# LCD_ctrl_v2b.net
KiCad netlist of a schematic drawn in EAGLE
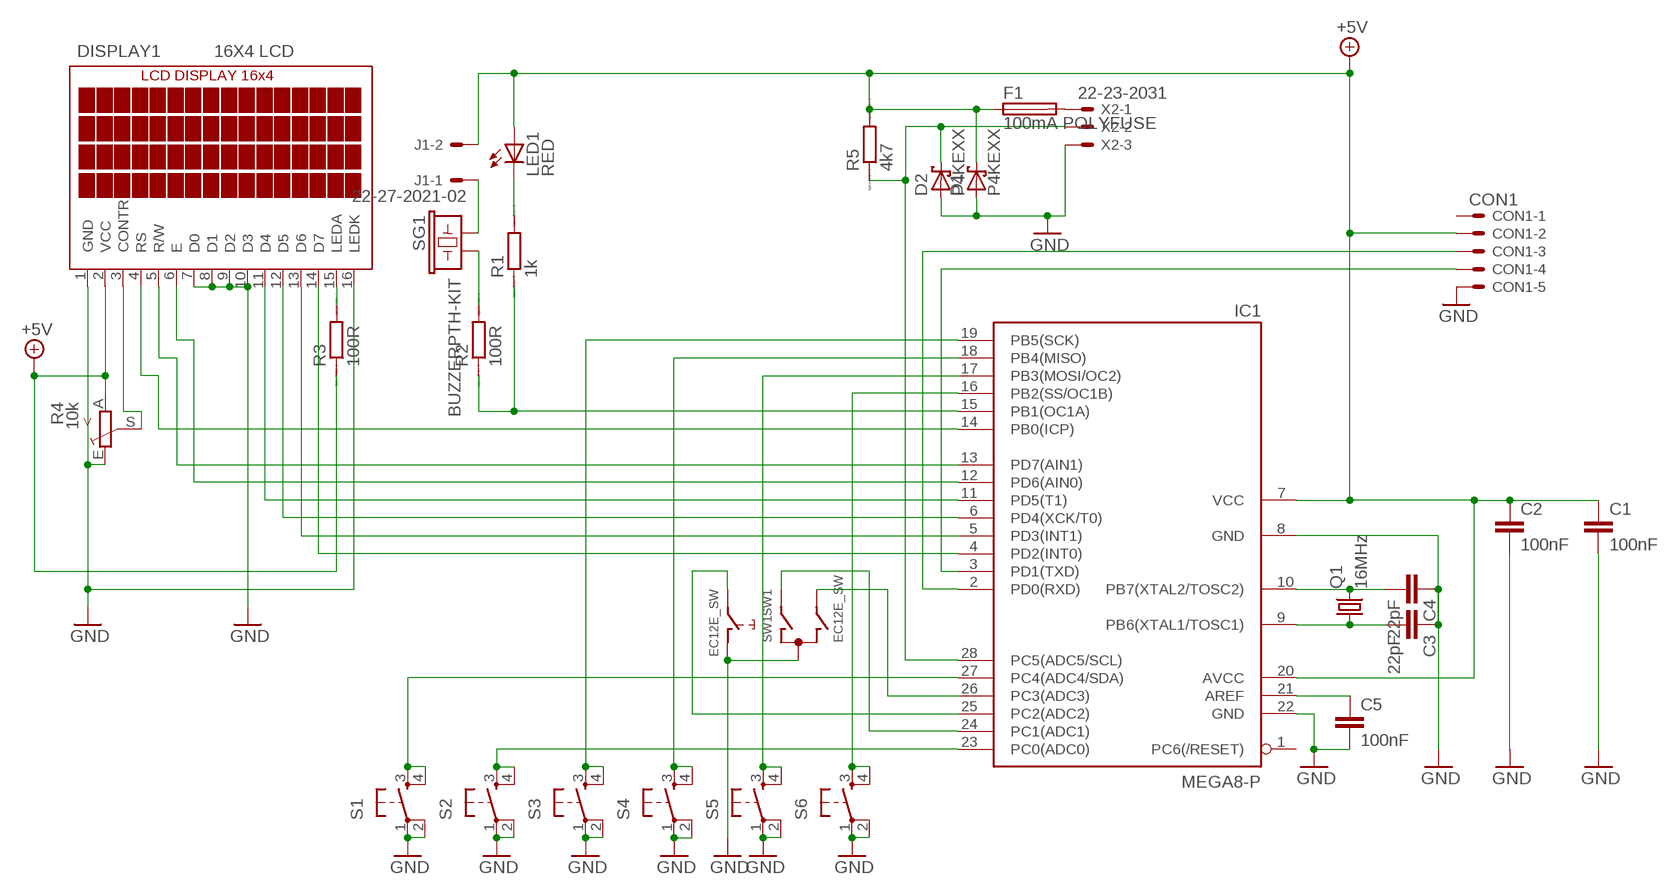
[diagram p0: schematic, sheet 1]

(export (version "E")
  (design (tool "Eeschema 10.0.6"))
  (components
    (comp (ref "C1")
      (value "100nF")
      (footprint "eagle-import:C050-025X075")
      (libsource (lib "eagle-import") (part "C-EU050-025X075"))
    )
    (comp (ref "C2")
      (value "100nF")
      (footprint "eagle-import:C050-025X075")
      (libsource (lib "eagle-import") (part "C-EU050-025X075"))
    )
    (comp (ref "C3")
      (value "22pF")
      (footprint "eagle-import:C050-025X075")
      (libsource (lib "eagle-import") (part "C-EU050-025X075"))
    )
    (comp (ref "C4")
      (value "22pF")
      (footprint "eagle-import:C050-025X075")
      (libsource (lib "eagle-import") (part "C-EU050-025X075"))
    )
    (comp (ref "C5")
      (value "100nF")
      (footprint "eagle-import:C050-025X075")
      (libsource (lib "eagle-import") (part "C-EU050-025X075"))
    )
    (comp (ref "CON1")
      (value "CON1")
      (footprint "eagle-import:22-23-2051")
      (fields (field (name "MF") "MOLEX") (field (name "MPN") "22-23-2051"))
      (libsource (lib "eagle-import") (part "22-23-2051"))
    )
    (comp (ref "D1")
      (value "P4KEXX")
      (footprint "eagle-import:DO41-10")
      (libsource (lib "eagle-import") (part "P4KEXX"))
    )
    (comp (ref "D2")
      (value "P4KEXX")
      (footprint "eagle-import:DO41-10")
      (libsource (lib "eagle-import") (part "P4KEXX"))
    )
    (comp (ref "DISPLAY1")
      (value "16X4 LCD")
      (footprint "eagle-import:LCD-AC-1604A-BIG_PADS")
      (libsource (lib "eagle-import") (part "LCD-AC-1604A_BIG_PADS"))
    )
    (comp (ref "F1")
      (value "100mA POLYFUSE")
      (footprint "eagle-import:TE5")
      (libsource (lib "eagle-import") (part "TE5"))
    )
    (comp (ref "IC1")
      (value "MEGA8-P")
      (footprint "eagle-import:DIL28-3")
      (libsource (lib "eagle-import") (part "MEGA8-P"))
    )
    (comp (ref "J1")
      (value "22-27-2021-02")
      (footprint "eagle-import:6410-02")
      (libsource (lib "eagle-import") (part "22-?-0227-2021"))
    )
    (comp (ref "LED1")
      (value "RED")
      (footprint "eagle-import:LED3MM")
      (fields (field (name "MF") "VISHAY SEMICONDUCTOR"))
      (libsource (lib "eagle-import") (part "TLLR4400"))
    )
    (comp (ref "Q1")
      (value "16MHz")
      (footprint "eagle-import:HC49_S")
      (libsource (lib "eagle-import") (part "CRYSTALHC49S"))
    )
    (comp (ref "R1")
      (value "1k")
      (footprint "eagle-import:0204_7")
      (libsource (lib "eagle-import") (part "R0204/7"))
    )
    (comp (ref "R2")
      (value "100R")
      (footprint "eagle-import:0204_7")
      (libsource (lib "eagle-import") (part "R0204/7"))
    )
    (comp (ref "R3")
      (value "100R")
      (footprint "eagle-import:0204_7")
      (libsource (lib "eagle-import") (part "R0204/7"))
    )
    (comp (ref "R4")
      (value "10k")
      (footprint "eagle-import:CA6H")
      (libsource (lib "eagle-import") (part "TRIM_EU-CA6H"))
    )
    (comp (ref "R5")
      (value "4k7")
      (footprint "eagle-import:0204_7")
      (libsource (lib "eagle-import") (part "R0204/7"))
    )
    (comp (ref "S1")
      (value "TAC_SWITCHPTH")
      (footprint "eagle-import:TACTILE-PTHX")
      (libsource (lib "eagle-import") (part "TAC_SWITCHPTH"))
    )
    (comp (ref "S2")
      (value "TAC_SWITCHPTH")
      (footprint "eagle-import:TACTILE-PTHX")
      (libsource (lib "eagle-import") (part "TAC_SWITCHPTH"))
    )
    (comp (ref "S3")
      (value "TAC_SWITCHPTH")
      (footprint "eagle-import:TACTILE-PTHX")
      (libsource (lib "eagle-import") (part "TAC_SWITCHPTH"))
    )
    (comp (ref "S4")
      (value "TAC_SWITCHPTH")
      (footprint "eagle-import:TACTILE-PTHX")
      (libsource (lib "eagle-import") (part "TAC_SWITCHPTH"))
    )
    (comp (ref "S5")
      (value "TAC_SWITCHPTH")
      (footprint "eagle-import:TACTILE-PTHX")
      (libsource (lib "eagle-import") (part "TAC_SWITCHPTH"))
    )
    (comp (ref "S6")
      (value "TAC_SWITCHPTH")
      (footprint "eagle-import:TACTILE-PTHX")
      (libsource (lib "eagle-import") (part "TAC_SWITCHPTH"))
    )
    (comp (ref "SG1")
      (value "BUZZERPTH-KIT")
      (footprint "eagle-import:BUZZER-12MM-KIT")
      (libsource (lib "eagle-import") (part "BUZZERPTH-KIT"))
    )
    (comp (ref "SW1")
      (value "EC12E_SW")
      (footprint "eagle-import:ALPS_EC12E_SW")
      (fields (field (name "MPN") "EC12E2424407"))
      (libsource (lib "eagle-import") (part "EC12E_SW"))
    )
    (comp (ref "X2")
      (value "22-23-2031")
      (footprint "eagle-import:22-23-2031")
      (fields (field (name "MF") "MOLEX"))
      (libsource (lib "eagle-import") (part "22-23-2031"))
    )
  )
  (nets
    (net (code "1") (name "+5V") (class "Default")
      (node (ref "C1") (pin "1") (pinfunction "1_1") (pintype "passive"))
      (node (ref "C2") (pin "1") (pinfunction "1_1") (pintype "passive"))
      (node (ref "CON1") (pin "2") (pinfunction "S_2") (pintype "passive"))
      (node (ref "D1") (pin "C") (pinfunction "C_C") (pintype "passive"))
      (node (ref "DISPLAY1") (pin "2") (pinfunction "VCC_2") (pintype "power_in"))
      (node (ref "F1") (pin "1") (pinfunction "1_1") (pintype "passive"))
      (node (ref "IC1") (pin "20") (pinfunction "AVCC_20") (pintype "power_in"))
      (node (ref "IC1") (pin "7") (pinfunction "VCC_7") (pintype "power_in"))
      (node (ref "J1") (pin "2") (pinfunction "S_2") (pintype "passive"))
      (node (ref "LED1") (pin "A") (pinfunction "A_A") (pintype "passive"))
      (node (ref "R3") (pin "1") (pinfunction "1_1") (pintype "passive"))
      (node (ref "R4") (pin "A") (pinfunction "A_A") (pintype "passive"))
      (node (ref "R5") (pin "2") (pinfunction "2_2") (pintype "passive"))
    )
    (net (code "2") (name "GND") (class "Default")
      (node (ref "C1") (pin "2") (pinfunction "2_2") (pintype "passive"))
      (node (ref "C2") (pin "2") (pinfunction "2_2") (pintype "passive"))
      (node (ref "C3") (pin "1") (pinfunction "1_1") (pintype "passive"))
      (node (ref "C4") (pin "1") (pinfunction "1_1") (pintype "passive"))
      (node (ref "C5") (pin "2") (pinfunction "2_2") (pintype "passive"))
      (node (ref "CON1") (pin "5") (pinfunction "S_5") (pintype "passive"))
      (node (ref "D1") (pin "A") (pinfunction "A_A") (pintype "passive"))
      (node (ref "D2") (pin "A") (pinfunction "A_A") (pintype "passive"))
      (node (ref "DISPLAY1") (pin "1") (pinfunction "GND_1") (pintype "power_in"))
      (node (ref "DISPLAY1") (pin "10") (pinfunction "D3_10") (pintype "input"))
      (node (ref "DISPLAY1") (pin "16") (pinfunction "LEDK_16") (pintype "power_in"))
      (node (ref "DISPLAY1") (pin "7") (pinfunction "D0_7") (pintype "input"))
      (node (ref "DISPLAY1") (pin "8") (pinfunction "D1_8") (pintype "input"))
      (node (ref "DISPLAY1") (pin "9") (pinfunction "D2_9") (pintype "input"))
      (node (ref "IC1") (pin "22") (pinfunction "GND_22") (pintype "power_in"))
      (node (ref "IC1") (pin "8") (pinfunction "GND_8") (pintype "power_in"))
      (node (ref "R4") (pin "E") (pinfunction "E_E") (pintype "passive"))
      (node (ref "S1") (pin "1") (pinfunction "1_1") (pintype "passive"))
      (node (ref "S1") (pin "2") (pinfunction "2_2") (pintype "passive"))
      (node (ref "S2") (pin "1") (pinfunction "1_1") (pintype "passive"))
      (node (ref "S2") (pin "2") (pinfunction "2_2") (pintype "passive"))
      (node (ref "S3") (pin "1") (pinfunction "1_1") (pintype "passive"))
      (node (ref "S3") (pin "2") (pinfunction "2_2") (pintype "passive"))
      (node (ref "S4") (pin "1") (pinfunction "1_1") (pintype "passive"))
      (node (ref "S4") (pin "2") (pinfunction "2_2") (pintype "passive"))
      (node (ref "S5") (pin "1") (pinfunction "1_1") (pintype "passive"))
      (node (ref "S5") (pin "2") (pinfunction "2_2") (pintype "passive"))
      (node (ref "S6") (pin "1") (pinfunction "1_1") (pintype "passive"))
      (node (ref "S6") (pin "2") (pinfunction "2_2") (pintype "passive"))
      (node (ref "SW1") (pin "C") (pinfunction "C_C") (pintype "passive"))
      (node (ref "SW1") (pin "D") (pinfunction "1_D") (pintype "passive"))
      (node (ref "X2") (pin "3") (pinfunction "S_3") (pintype "passive"))
    )
    (net (code "3") (name "Net-(CON1C-S)") (class "Default")
      (node (ref "CON1") (pin "3") (pinfunction "S_3") (pintype "passive"))
      (node (ref "IC1") (pin "2") (pinfunction "PD0(RXD)_2") (pintype "bidirectional"))
    )
    (net (code "4") (name "Net-(CON1D-S)") (class "Default")
      (node (ref "CON1") (pin "4") (pinfunction "S_4") (pintype "passive"))
      (node (ref "IC1") (pin "3") (pinfunction "PD1(TXD)_3") (pintype "bidirectional"))
    )
    (net (code "5") (name "Net-(DISPLAY1-CONTR)") (class "Default")
      (node (ref "DISPLAY1") (pin "3") (pinfunction "CONTR_3") (pintype "input"))
      (node (ref "R4") (pin "S") (pinfunction "S_S") (pintype "passive"))
    )
    (net (code "6") (name "Net-(DISPLAY1-D4)") (class "Default")
      (node (ref "DISPLAY1") (pin "11") (pinfunction "D4_11") (pintype "input"))
      (node (ref "IC1") (pin "11") (pinfunction "PD5(T1)_11") (pintype "bidirectional"))
    )
    (net (code "7") (name "Net-(DISPLAY1-D5)") (class "Default")
      (node (ref "DISPLAY1") (pin "12") (pinfunction "D5_12") (pintype "input"))
      (node (ref "IC1") (pin "6") (pinfunction "PD4(XCK/T0)_6") (pintype "bidirectional"))
    )
    (net (code "8") (name "Net-(DISPLAY1-D6)") (class "Default")
      (node (ref "DISPLAY1") (pin "13") (pinfunction "D6_13") (pintype "input"))
      (node (ref "IC1") (pin "5") (pinfunction "PD3(INT1)_5") (pintype "bidirectional"))
    )
    (net (code "9") (name "Net-(DISPLAY1-D7)") (class "Default")
      (node (ref "DISPLAY1") (pin "14") (pinfunction "D7_14") (pintype "input"))
      (node (ref "IC1") (pin "4") (pinfunction "PD2(INT0)_4") (pintype "bidirectional"))
    )
    (net (code "10") (name "Net-(DISPLAY1-E)") (class "Default")
      (node (ref "DISPLAY1") (pin "6") (pinfunction "E_6") (pintype "input"))
      (node (ref "IC1") (pin "12") (pinfunction "PD6(AIN0)_12") (pintype "bidirectional"))
    )
    (net (code "11") (name "Net-(DISPLAY1-LEDA)") (class "Default")
      (node (ref "DISPLAY1") (pin "15") (pinfunction "LEDA_15") (pintype "power_in"))
      (node (ref "R3") (pin "2") (pinfunction "2_2") (pintype "passive"))
    )
    (net (code "12") (name "Net-(DISPLAY1-RS)") (class "Default")
      (node (ref "DISPLAY1") (pin "4") (pinfunction "RS_4") (pintype "input"))
      (node (ref "IC1") (pin "14") (pinfunction "PB0(ICP)_14") (pintype "bidirectional"))
    )
    (net (code "13") (name "Net-(DISPLAY1-R{slash}W)") (class "Default")
      (node (ref "DISPLAY1") (pin "5") (pinfunction "R/W_5") (pintype "input"))
      (node (ref "IC1") (pin "13") (pinfunction "PD7(AIN1)_13") (pintype "bidirectional"))
    )
    (net (code "14") (name "Net-(IC1-AREF)") (class "Default")
      (node (ref "C5") (pin "1") (pinfunction "1_1") (pintype "passive"))
      (node (ref "IC1") (pin "21") (pinfunction "AREF_21") (pintype "passive"))
    )
    (net (code "15") (name "Net-(IC1-PB1(OC1A))") (class "Default")
      (node (ref "IC1") (pin "15") (pinfunction "PB1(OC1A)_15") (pintype "bidirectional"))
      (node (ref "R1") (pin "1") (pinfunction "1_1") (pintype "passive"))
      (node (ref "R2") (pin "1") (pinfunction "1_1") (pintype "passive"))
    )
    (net (code "16") (name "Net-(IC1-PB2(SS{slash}OC1B))") (class "Default")
      (node (ref "IC1") (pin "16") (pinfunction "PB2(SS/OC1B)_16") (pintype "bidirectional"))
      (node (ref "S6") (pin "3") (pinfunction "3_3") (pintype "passive"))
      (node (ref "S6") (pin "4") (pinfunction "4_4") (pintype "passive"))
    )
    (net (code "17") (name "Net-(IC1-PB3(MOSI{slash}OC2))") (class "Default")
      (node (ref "IC1") (pin "17") (pinfunction "PB3(MOSI/OC2)_17") (pintype "bidirectional"))
      (node (ref "S5") (pin "3") (pinfunction "3_3") (pintype "passive"))
      (node (ref "S5") (pin "4") (pinfunction "4_4") (pintype "passive"))
    )
    (net (code "18") (name "Net-(IC1-PB4(MISO))") (class "Default")
      (node (ref "IC1") (pin "18") (pinfunction "PB4(MISO)_18") (pintype "bidirectional"))
      (node (ref "S4") (pin "3") (pinfunction "3_3") (pintype "passive"))
      (node (ref "S4") (pin "4") (pinfunction "4_4") (pintype "passive"))
    )
    (net (code "19") (name "Net-(IC1-PB5(SCK))") (class "Default")
      (node (ref "IC1") (pin "19") (pinfunction "PB5(SCK)_19") (pintype "bidirectional"))
      (node (ref "S3") (pin "3") (pinfunction "3_3") (pintype "passive"))
      (node (ref "S3") (pin "4") (pinfunction "4_4") (pintype "passive"))
    )
    (net (code "20") (name "Net-(IC1-PB6(XTAL1{slash}TOSC1))") (class "Default")
      (node (ref "C3") (pin "2") (pinfunction "2_2") (pintype "passive"))
      (node (ref "IC1") (pin "9") (pinfunction "PB6(XTAL1/TOSC1)_9") (pintype "bidirectional"))
      (node (ref "Q1") (pin "1") (pinfunction "1_1") (pintype "passive"))
    )
    (net (code "21") (name "Net-(IC1-PB7(XTAL2{slash}TOSC2))") (class "Default")
      (node (ref "C4") (pin "2") (pinfunction "2_2") (pintype "passive"))
      (node (ref "IC1") (pin "10") (pinfunction "PB7(XTAL2/TOSC2)_10") (pintype "bidirectional"))
      (node (ref "Q1") (pin "2") (pinfunction "2_2") (pintype "passive"))
    )
    (net (code "22") (name "Net-(IC1-PC0(ADC0))") (class "Default")
      (node (ref "IC1") (pin "23") (pinfunction "PC0(ADC0)_23") (pintype "bidirectional"))
      (node (ref "S2") (pin "3") (pinfunction "3_3") (pintype "passive"))
      (node (ref "S2") (pin "4") (pinfunction "4_4") (pintype "passive"))
    )
    (net (code "23") (name "Net-(IC1-PC1(ADC1))") (class "Default")
      (node (ref "IC1") (pin "24") (pinfunction "PC1(ADC1)_24") (pintype "bidirectional"))
      (node (ref "SW1") (pin "A") (pinfunction "A_A") (pintype "passive"))
    )
    (net (code "24") (name "Net-(IC1-PC2(ADC2))") (class "Default")
      (node (ref "IC1") (pin "25") (pinfunction "PC2(ADC2)_25") (pintype "bidirectional"))
      (node (ref "SW1") (pin "E") (pinfunction "2_E") (pintype "passive"))
    )
    (net (code "25") (name "Net-(IC1-PC3(ADC3))") (class "Default")
      (node (ref "IC1") (pin "26") (pinfunction "PC3(ADC3)_26") (pintype "bidirectional"))
      (node (ref "SW1") (pin "B") (pinfunction "B_B") (pintype "passive"))
    )
    (net (code "26") (name "Net-(IC1-PC4(ADC4{slash}SDA))") (class "Default")
      (node (ref "IC1") (pin "27") (pinfunction "PC4(ADC4/SDA)_27") (pintype "bidirectional"))
      (node (ref "S1") (pin "3") (pinfunction "3_3") (pintype "passive"))
      (node (ref "S1") (pin "4") (pinfunction "4_4") (pintype "passive"))
    )
    (net (code "27") (name "Net-(IC1-PC5(ADC5{slash}SCL))") (class "Default")
      (node (ref "D2") (pin "C") (pinfunction "C_C") (pintype "passive"))
      (node (ref "IC1") (pin "28") (pinfunction "PC5(ADC5/SCL)_28") (pintype "bidirectional"))
      (node (ref "R5") (pin "1") (pinfunction "1_1") (pintype "passive"))
      (node (ref "X2") (pin "2") (pinfunction "S_2") (pintype "passive"))
    )
    (net (code "28") (name "Net-(J1A-S)") (class "Default")
      (node (ref "J1") (pin "1") (pinfunction "S_1") (pintype "passive"))
      (node (ref "SG1") (pin "+") (pinfunction "1_+") (pintype "passive"))
    )
    (net (code "29") (name "Net-(LED1-C)") (class "Default")
      (node (ref "LED1") (pin "K") (pinfunction "C_K") (pintype "passive"))
      (node (ref "R1") (pin "2") (pinfunction "2_2") (pintype "passive"))
    )
    (net (code "30") (name "Net-(SG1-2)") (class "Default")
      (node (ref "R2") (pin "2") (pinfunction "2_2") (pintype "passive"))
      (node (ref "SG1") (pin "-") (pinfunction "2_-") (pintype "passive"))
    )
    (net (code "31") (name "Net-(X2A-S)") (class "Default")
      (node (ref "F1") (pin "2") (pinfunction "2_2") (pintype "passive"))
      (node (ref "X2") (pin "1") (pinfunction "S_1") (pintype "passive"))
    )
    (net (code "32") (name "unconnected-(CON1A-S-Pad1)") (class "Default")
      (node (ref "CON1") (pin "1") (pinfunction "S_1") (pintype "passive"))
    )
    (net (code "33") (name "unconnected-(IC1-PC6({slash}RESET)-Pad1)") (class "Default")
      (node (ref "IC1") (pin "1") (pinfunction "PC6(/RESET)_1") (pintype "bidirectional"))
    )
  )
)
